# SCH_nfc-card_2024-10-29_2.net
KiCad netlist of a schematic drawn in EasyEDA
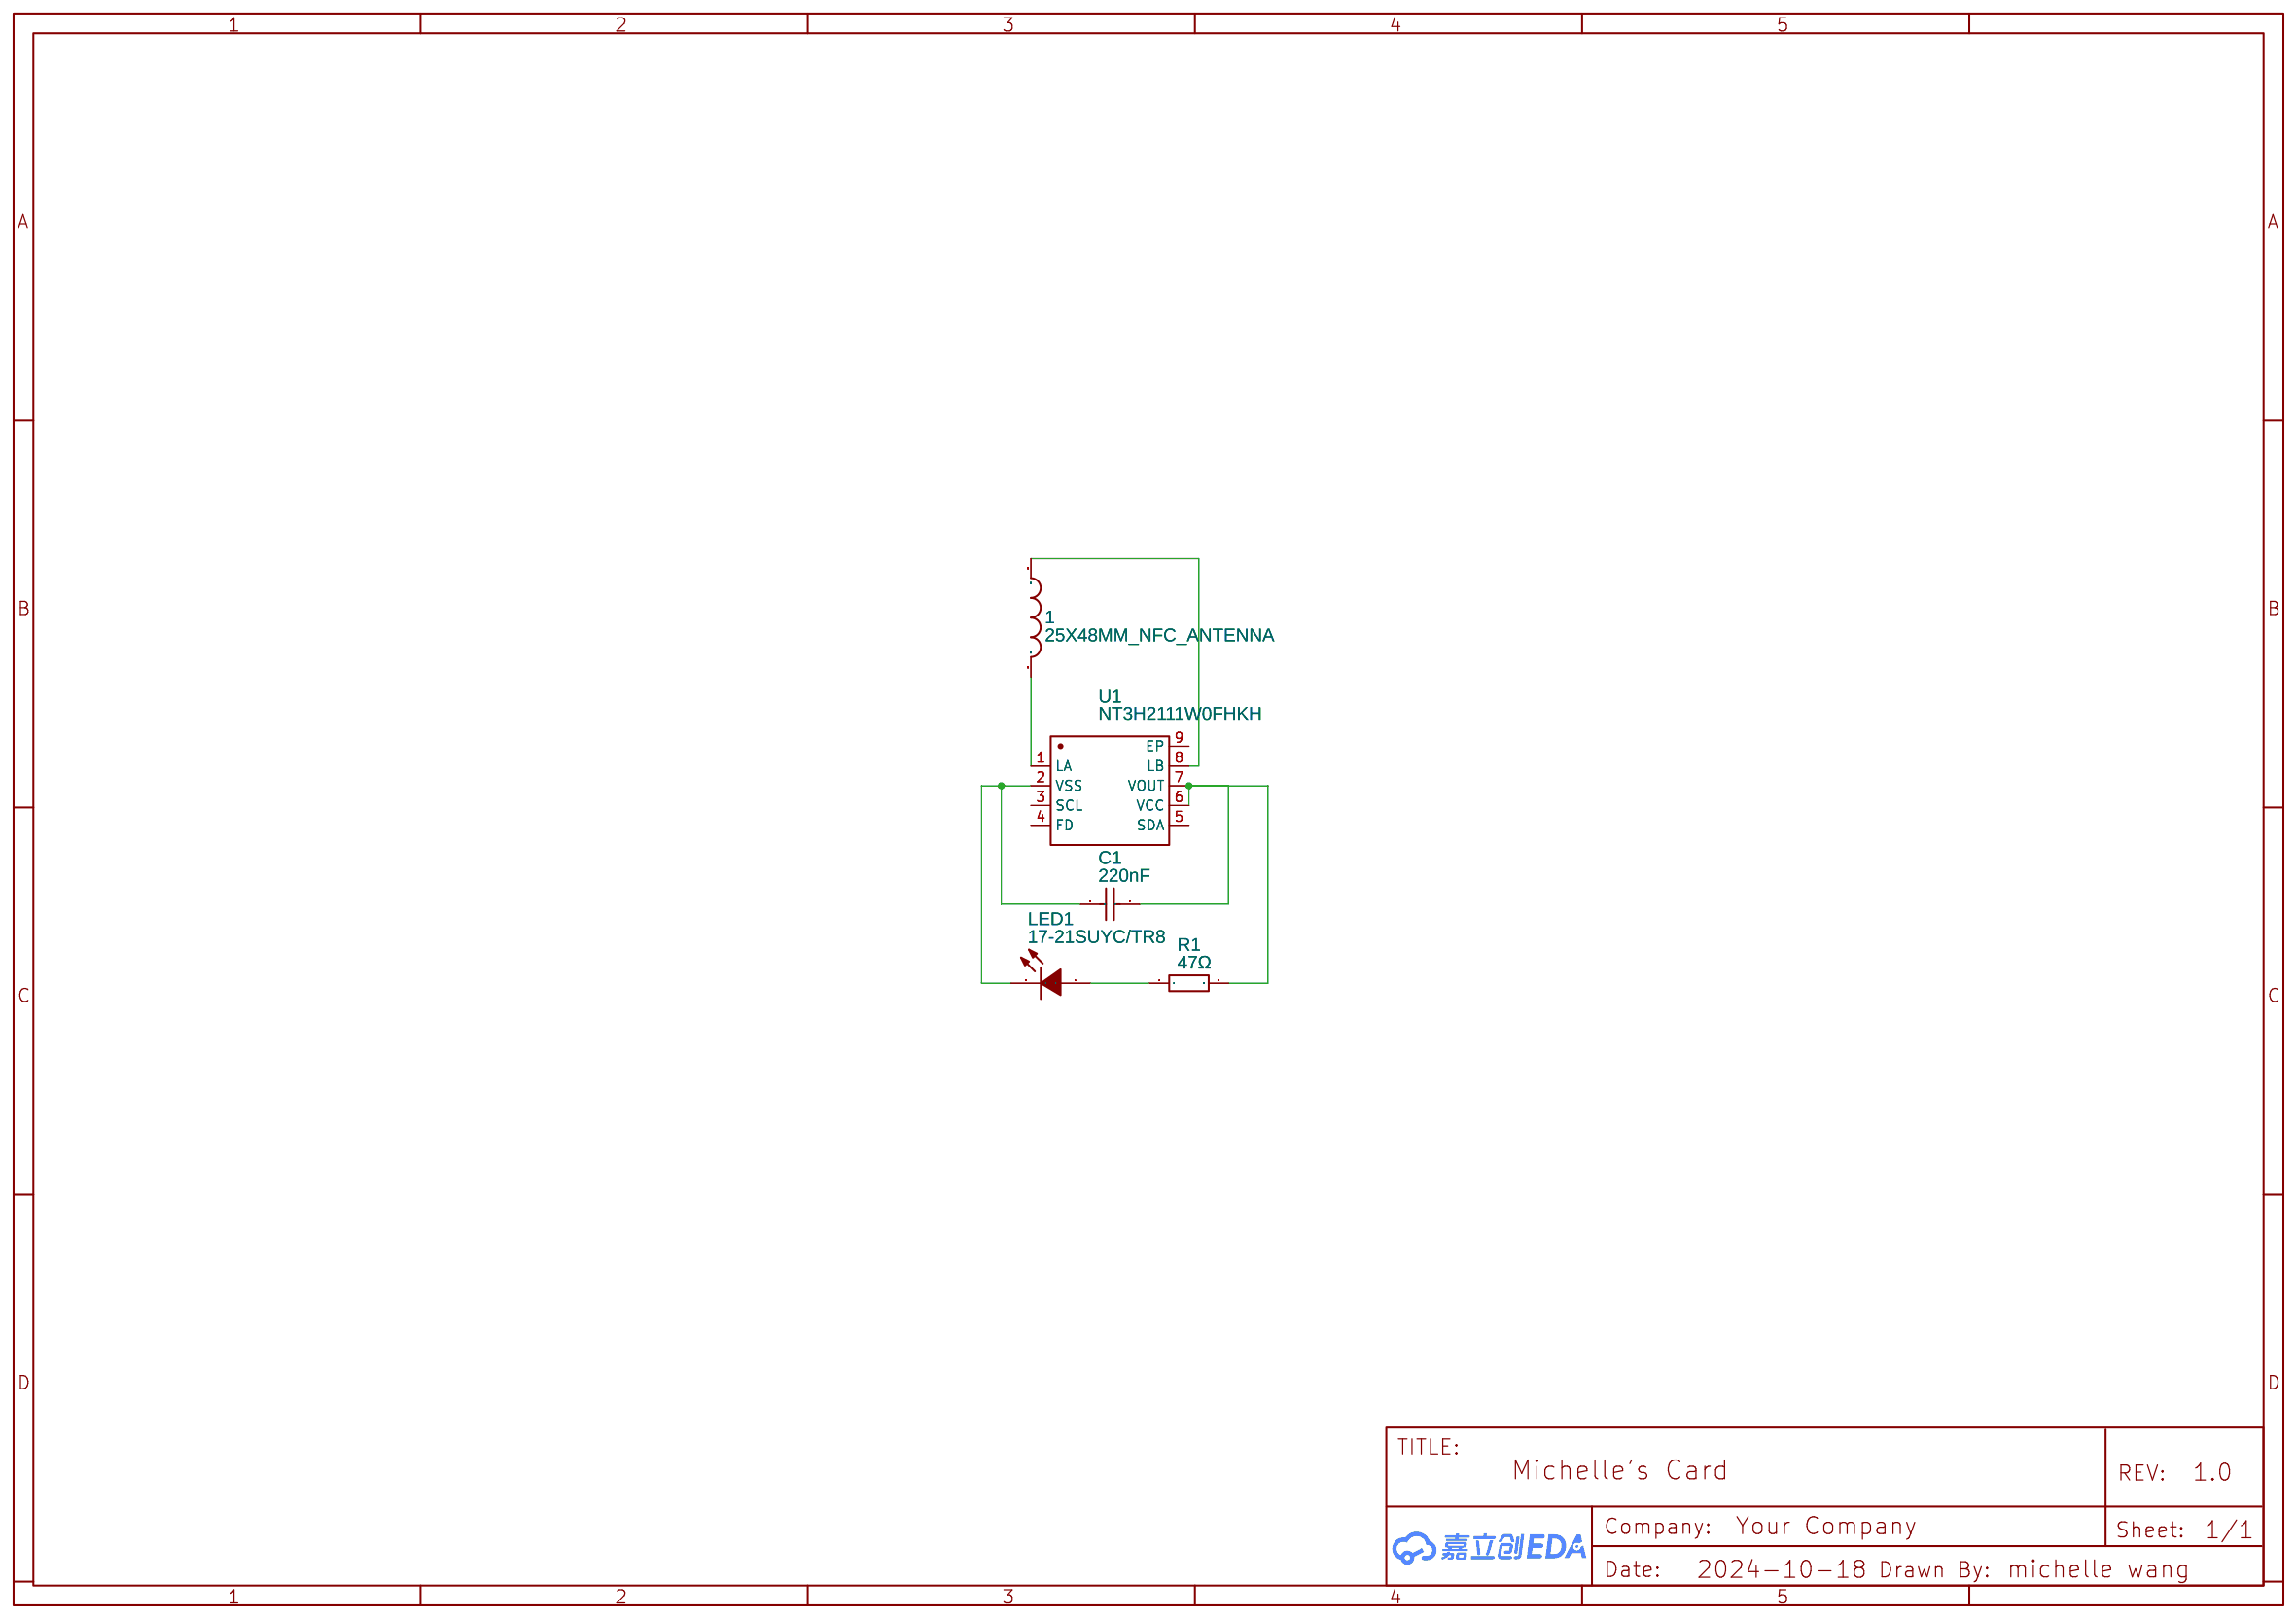
[diagram p0: schematic sheet]

(export (version "E")
  (design (tool "Eeschema 10.0.6"))
  (components
    (comp (ref "1") (value "25X48MM_NFC_ANTENNA") (libsource (lib "") (part "25X48MM_NFC_ANTENNA")))
    (comp (ref "C1")
      (value "220nF")
      (fields
        (field (name "Manufacturer Part") "CL10B224KA8NNNC")
        (field (name "Manufacturer") "SAMSUNG(三星)")
      )
      (libsource (lib "") (part "CL10B224KA8NNNC"))
    )
    (comp (ref "LED1")
      (value "17-21SUYC/TR8")
      (fields (field (name "Manufacturer Part") "KT-0805黄灯") (field (name "Manufacturer") "KENTO"))
      (libsource (lib "") (part "17-21SUYC/TR8"))
    )
    (comp (ref "R1")
      (value "47Ω")
      (fields
        (field (name "Manufacturer Part") "0603WAF470JT5E")
        (field (name "Manufacturer") "UNI-ROYAL(厚声)")
      )
      (libsource (lib "") (part "0603WAF470JT5E"))
    )
    (comp (ref "U1")
      (value "NT3H2111W0FHKH")
      (fields (field (name "Manufacturer") "NXP(恩智浦)"))
      (libsource (lib "") (part "NT3H2111W0FHKH"))
    )
  )
  (nets
    (net (code "1") (name "Net-(LED1-+)") (class "Default")
      (node (ref "LED1") (pin "1") (pinfunction "+_1") (pintype "unspecified"))
      (node (ref "R1") (pin "1") (pinfunction "1_1") (pintype "input"))
    )
    (net (code "2") (name "Net-(LED1--)") (class "Default")
      (node (ref "C1") (pin "1") (pinfunction "1_1") (pintype "input"))
      (node (ref "LED1") (pin "2") (pinfunction "-_2") (pintype "unspecified"))
      (node (ref "U1") (pin "2") (pinfunction "VSS_2") (pintype "unspecified"))
    )
    (net (code "3") (name "Net-(U1-LA)") (class "Default")
      (node (ref "1") (pin "P$2") (pinfunction "P$2_P$2") (pintype "bidirectional"))
      (node (ref "U1") (pin "1") (pinfunction "LA_1") (pintype "unspecified"))
    )
    (net (code "4") (name "Net-(U1-LB)") (class "Default")
      (node (ref "1") (pin "P$1") (pinfunction "P$1_P$1") (pintype "bidirectional"))
      (node (ref "U1") (pin "8") (pinfunction "LB_8") (pintype "unspecified"))
    )
    (net (code "5") (name "Net-(U1-VCC)") (class "Default")
      (node (ref "C1") (pin "2") (pinfunction "2_2") (pintype "input"))
      (node (ref "R1") (pin "2") (pinfunction "2_2") (pintype "input"))
      (node (ref "U1") (pin "6") (pinfunction "VCC_6") (pintype "unspecified"))
      (node (ref "U1") (pin "7") (pinfunction "VOUT_7") (pintype "unspecified"))
    )
    (net (code "6") (name "unconnected-(U1-EP-Pad9)") (class "Default")
      (node (ref "U1") (pin "9") (pinfunction "EP_9") (pintype "unspecified"))
    )
    (net (code "7") (name "unconnected-(U1-FD-Pad4)") (class "Default")
      (node (ref "U1") (pin "4") (pinfunction "FD_4") (pintype "unspecified"))
    )
    (net (code "8") (name "unconnected-(U1-SCL-Pad3)") (class "Default")
      (node (ref "U1") (pin "3") (pinfunction "SCL_3") (pintype "unspecified"))
    )
    (net (code "9") (name "unconnected-(U1-SDA-Pad5)") (class "Default")
      (node (ref "U1") (pin "5") (pinfunction "SDA_5") (pintype "unspecified"))
    )
  )
)
